# Sensor.net
KiCad netlist of a schematic drawn in Altium Designer
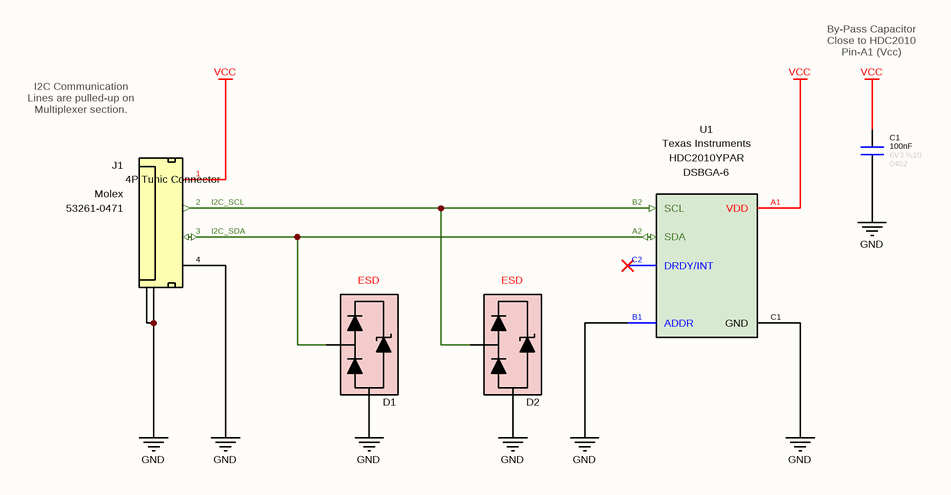
[diagram p0: Sensor.SchDoc]

(export (version "E")
  (design (tool "Eeschema 10.0.6"))
  (components
    (comp (ref "C1")
      (value "100nF")
      (footprint "CAPACITOR_0402")
      (description "Capacitor - 100nF [0402-6V3] (Ceramic)")
      (fields
        (field (name "MANUFACTURER PART NUMBER") "04026D104KAT4A")
        (field (name "TOLERANCE") "%10")
        (field (name "VOLTAGE") "6V3")
        (field (name "CASE") "0402")
        (field (name "Comment") "Capacitor - 100nF [0402] (Ceramic)")
      )
      (libsource (lib "P101DA_Library") (part "Capacitor - 100nF [0402-6V3]"))
    )
    (comp (ref "D1")
      (value "0402ESDA-MLP1")
      (footprint "ESD_0402")
      (description "SUPPRESSOR ESD 30VDC 0402 HFREE")
      (libsource (lib "P101DA_Library") (part "Diode - TPD1E05U06DPYR"))
    )
    (comp (ref "D2")
      (value "0402ESDA-MLP1")
      (footprint "ESD_0402")
      (description "SUPPRESSOR ESD 30VDC 0402 HFREE")
      (libsource (lib "P101DA_Library") (part "Diode - TPD1E05U06DPYR"))
    )
    (comp (ref "J1")
      (value "4P SMD Tunic Connector")
      (footprint "Connector_Tunic 4P")
      (description "Mini Tunic Connector with 4P")
      (fields
        (field (name "MANUFACTURER NAME") "Molex")
        (field (name "MANUFACTURER PART NUMBER") "53261-0471")
      )
      (libsource (lib "P101DA_Library") (part "Connector - Mini Tunic 4P (1.25)"))
    )
    (comp (ref "U1")
      (value "HDC2010YPAR")
      (footprint "HDC2010")
      (description "GEN 2 HUMIDITY SENSOR")
      (fields
        (field (name "MANUFACTURER NAME") "Texas Instruments")
        (field (name "MANUFACTURER PART NUMBER") "HDC2010YPAR")
        (field (name "CASE") "DSBGA-6")
      )
      (libsource (lib "P101DA_Library") (part "IC - HDC2010"))
    )
  )
  (nets
    (net (code "1") (name "/I2C_SCL") (class "Default")
      (node (ref "D2") (pin "1") (pinfunction "I/O_1") (pintype "passive"))
      (node (ref "J1") (pin "2") (pinfunction "Pin-2_2") (pintype "output"))
      (node (ref "U1") (pin "B2") (pinfunction "SCL_B2") (pintype "input"))
    )
    (net (code "2") (name "/I2C_SDA") (class "Default")
      (node (ref "D1") (pin "1") (pinfunction "I/O_1") (pintype "passive"))
      (node (ref "J1") (pin "3") (pinfunction "Pin-3_3") (pintype "bidirectional"))
      (node (ref "U1") (pin "A2") (pinfunction "SDA_A2") (pintype "bidirectional"))
    )
    (net (code "3") (name "GND") (class "Default")
      (node (ref "C1") (pin "1") (pinfunction "1_1") (pintype "passive"))
      (node (ref "D1") (pin "2") (pinfunction "GND_2") (pintype "passive"))
      (node (ref "D2") (pin "2") (pinfunction "GND_2") (pintype "passive"))
      (node (ref "J1") (pin "4") (pinfunction "Pin-4_4") (pintype "power_in"))
      (node (ref "J1") (pin "5") (pinfunction "GND_5") (pintype "passive"))
      (node (ref "J1") (pin "6") (pinfunction "GND_6") (pintype "passive"))
      (node (ref "U1") (pin "B1") (pinfunction "ADDR_B1") (pintype "passive"))
      (node (ref "U1") (pin "C1") (pinfunction "GND_C1") (pintype "power_in"))
    )
    (net (code "4") (name "VCC") (class "Default")
      (node (ref "C1") (pin "2") (pinfunction "2_2") (pintype "passive"))
      (node (ref "J1") (pin "1") (pinfunction "Pin-1_1") (pintype "power_in"))
      (node (ref "U1") (pin "A1") (pinfunction "VDD_A1") (pintype "power_in"))
    )
    (net (code "5") (name "unconnected-(U1-DRDY{slash}INT-PadC2)") (class "Default")
      (node (ref "U1") (pin "C2") (pinfunction "DRDY/INT_C2") (pintype "passive+no_connect"))
    )
  )
)
